# Switches.net
KiCad netlist of a schematic drawn in Altium Designer
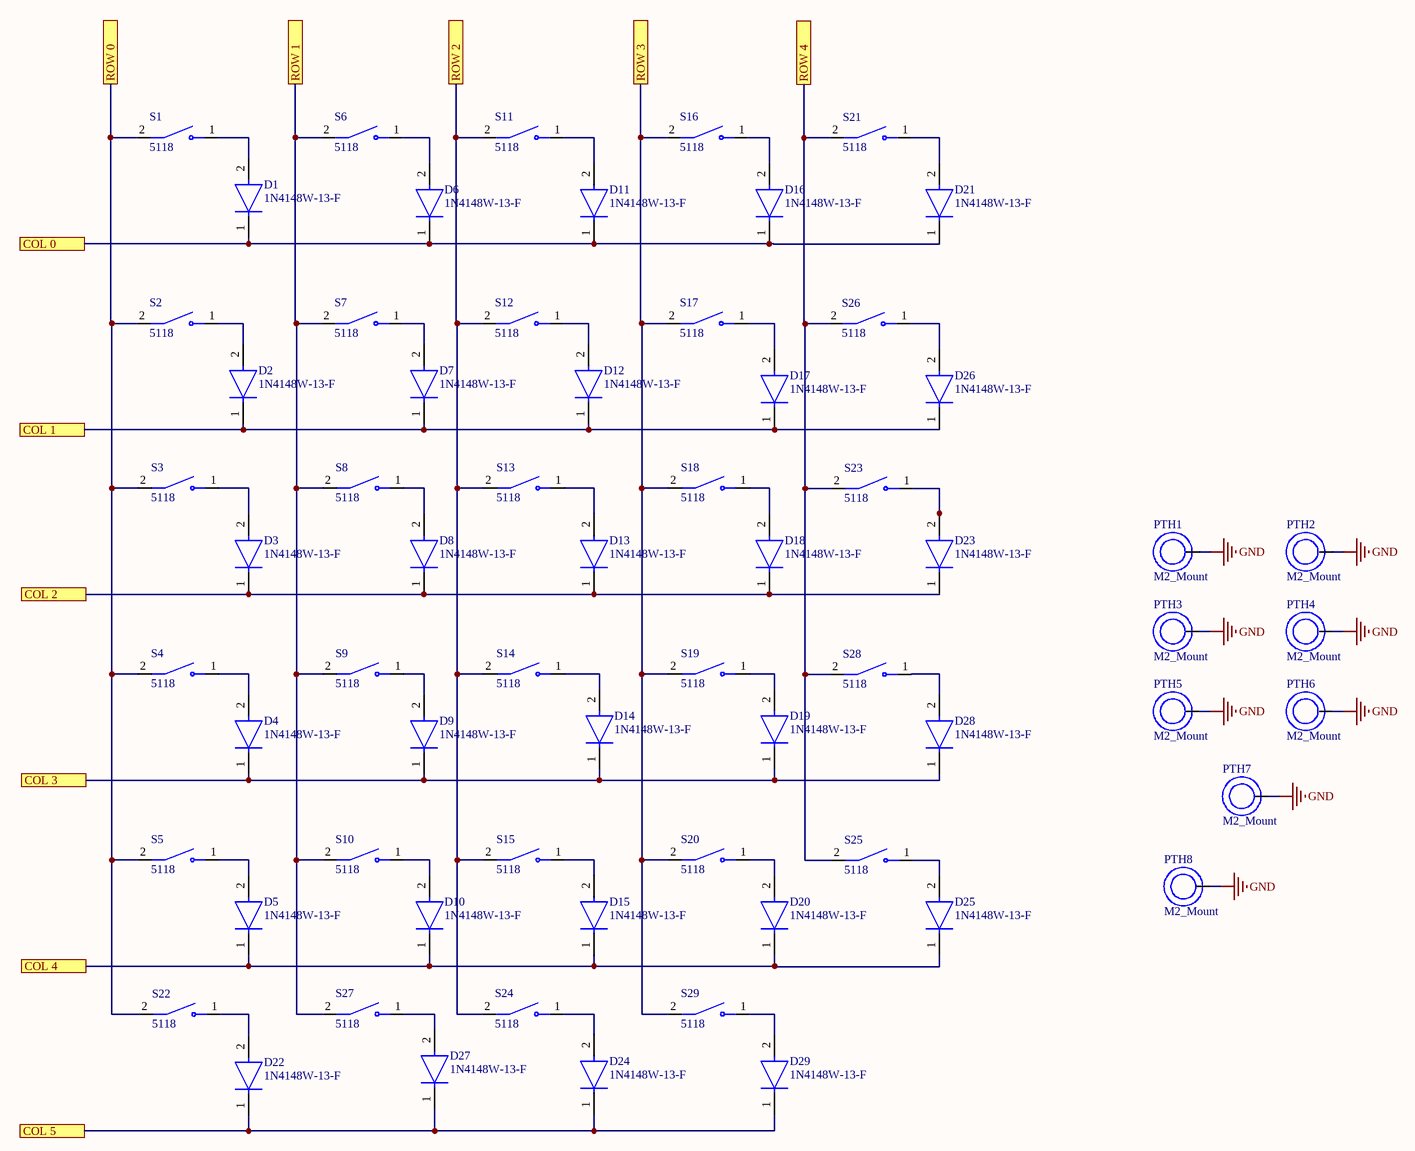
[diagram p0: Switches.SchDoc]

(export (version "E")
  (design (tool "Eeschema 10.0.6"))
  (components
    (comp (ref "D1")
      (value "1N4148W-13-F")
      (footprint "FP-SOD123-MFG")
      (description "DIODE GEN PURP 100V 150MA SOD123")
      (fields
        (field (name "OCTOPART") "https://octopart.com/1n4148w-13-f-diodes+inc.-2359612")
        (field (name "MANUFACTURER") "Diodes Inc.")
      )
      (libsource (lib "Altium Content Vault") (part "d7152d700b627762746794eb795d46e"))
    )
    (comp (ref "D2")
      (value "1N4148W-13-F")
      (footprint "FP-SOD123-MFG")
      (description "DIODE GEN PURP 100V 150MA SOD123")
      (fields
        (field (name "OCTOPART") "https://octopart.com/1n4148w-13-f-diodes+inc.-2359612")
        (field (name "MANUFACTURER") "Diodes Inc.")
      )
      (libsource (lib "Altium Content Vault") (part "d7152d700b627762746794eb795d46e"))
    )
    (comp (ref "D3")
      (value "1N4148W-13-F")
      (footprint "FP-SOD123-MFG")
      (description "DIODE GEN PURP 100V 150MA SOD123")
      (fields
        (field (name "OCTOPART") "https://octopart.com/1n4148w-13-f-diodes+inc.-2359612")
        (field (name "MANUFACTURER") "Diodes Inc.")
      )
      (libsource (lib "Altium Content Vault") (part "d7152d700b627762746794eb795d46e"))
    )
    (comp (ref "D4")
      (value "1N4148W-13-F")
      (footprint "FP-SOD123-MFG")
      (description "DIODE GEN PURP 100V 150MA SOD123")
      (fields
        (field (name "OCTOPART") "https://octopart.com/1n4148w-13-f-diodes+inc.-2359612")
        (field (name "MANUFACTURER") "Diodes Inc.")
      )
      (libsource (lib "Altium Content Vault") (part "d7152d700b627762746794eb795d46e"))
    )
    (comp (ref "D5")
      (value "1N4148W-13-F")
      (footprint "FP-SOD123-MFG")
      (description "DIODE GEN PURP 100V 150MA SOD123")
      (fields
        (field (name "OCTOPART") "https://octopart.com/1n4148w-13-f-diodes+inc.-2359612")
        (field (name "MANUFACTURER") "Diodes Inc.")
      )
      (libsource (lib "Altium Content Vault") (part "d7152d700b627762746794eb795d46e"))
    )
    (comp (ref "D6")
      (value "1N4148W-13-F")
      (footprint "FP-SOD123-MFG")
      (description "DIODE GEN PURP 100V 150MA SOD123")
      (fields
        (field (name "OCTOPART") "https://octopart.com/1n4148w-13-f-diodes+inc.-2359612")
        (field (name "MANUFACTURER") "Diodes Inc.")
      )
      (libsource (lib "Altium Content Vault") (part "d7152d700b627762746794eb795d46e"))
    )
    (comp (ref "D7")
      (value "1N4148W-13-F")
      (footprint "FP-SOD123-MFG")
      (description "DIODE GEN PURP 100V 150MA SOD123")
      (fields
        (field (name "OCTOPART") "https://octopart.com/1n4148w-13-f-diodes+inc.-2359612")
        (field (name "MANUFACTURER") "Diodes Inc.")
      )
      (libsource (lib "Altium Content Vault") (part "d7152d700b627762746794eb795d46e"))
    )
    (comp (ref "D8")
      (value "1N4148W-13-F")
      (footprint "FP-SOD123-MFG")
      (description "DIODE GEN PURP 100V 150MA SOD123")
      (fields
        (field (name "OCTOPART") "https://octopart.com/1n4148w-13-f-diodes+inc.-2359612")
        (field (name "MANUFACTURER") "Diodes Inc.")
      )
      (libsource (lib "Altium Content Vault") (part "d7152d700b627762746794eb795d46e"))
    )
    (comp (ref "D9")
      (value "1N4148W-13-F")
      (footprint "FP-SOD123-MFG")
      (description "DIODE GEN PURP 100V 150MA SOD123")
      (fields
        (field (name "OCTOPART") "https://octopart.com/1n4148w-13-f-diodes+inc.-2359612")
        (field (name "MANUFACTURER") "Diodes Inc.")
      )
      (libsource (lib "Altium Content Vault") (part "d7152d700b627762746794eb795d46e"))
    )
    (comp (ref "D10")
      (value "1N4148W-13-F")
      (footprint "FP-SOD123-MFG")
      (description "DIODE GEN PURP 100V 150MA SOD123")
      (fields
        (field (name "OCTOPART") "https://octopart.com/1n4148w-13-f-diodes+inc.-2359612")
        (field (name "MANUFACTURER") "Diodes Inc.")
      )
      (libsource (lib "Altium Content Vault") (part "d7152d700b627762746794eb795d46e"))
    )
    (comp (ref "D11")
      (value "1N4148W-13-F")
      (footprint "FP-SOD123-MFG")
      (description "DIODE GEN PURP 100V 150MA SOD123")
      (fields
        (field (name "OCTOPART") "https://octopart.com/1n4148w-13-f-diodes+inc.-2359612")
        (field (name "MANUFACTURER") "Diodes Inc.")
      )
      (libsource (lib "Altium Content Vault") (part "d7152d700b627762746794eb795d46e"))
    )
    (comp (ref "D12")
      (value "1N4148W-13-F")
      (footprint "FP-SOD123-MFG")
      (description "DIODE GEN PURP 100V 150MA SOD123")
      (fields
        (field (name "OCTOPART") "https://octopart.com/1n4148w-13-f-diodes+inc.-2359612")
        (field (name "MANUFACTURER") "Diodes Inc.")
      )
      (libsource (lib "Altium Content Vault") (part "d7152d700b627762746794eb795d46e"))
    )
    (comp (ref "D13")
      (value "1N4148W-13-F")
      (footprint "FP-SOD123-MFG")
      (description "DIODE GEN PURP 100V 150MA SOD123")
      (fields
        (field (name "OCTOPART") "https://octopart.com/1n4148w-13-f-diodes+inc.-2359612")
        (field (name "MANUFACTURER") "Diodes Inc.")
      )
      (libsource (lib "Altium Content Vault") (part "d7152d700b627762746794eb795d46e"))
    )
    (comp (ref "D14")
      (value "1N4148W-13-F")
      (footprint "FP-SOD123-MFG")
      (description "DIODE GEN PURP 100V 150MA SOD123")
      (fields
        (field (name "OCTOPART") "https://octopart.com/1n4148w-13-f-diodes+inc.-2359612")
        (field (name "MANUFACTURER") "Diodes Inc.")
      )
      (libsource (lib "Altium Content Vault") (part "d7152d700b627762746794eb795d46e"))
    )
    (comp (ref "D15")
      (value "1N4148W-13-F")
      (footprint "FP-SOD123-MFG")
      (description "DIODE GEN PURP 100V 150MA SOD123")
      (fields
        (field (name "OCTOPART") "https://octopart.com/1n4148w-13-f-diodes+inc.-2359612")
        (field (name "MANUFACTURER") "Diodes Inc.")
      )
      (libsource (lib "Altium Content Vault") (part "d7152d700b627762746794eb795d46e"))
    )
    (comp (ref "D16")
      (value "1N4148W-13-F")
      (footprint "FP-SOD123-MFG")
      (description "DIODE GEN PURP 100V 150MA SOD123")
      (fields
        (field (name "OCTOPART") "https://octopart.com/1n4148w-13-f-diodes+inc.-2359612")
        (field (name "MANUFACTURER") "Diodes Inc.")
      )
      (libsource (lib "Altium Content Vault") (part "d7152d700b627762746794eb795d46e"))
    )
    (comp (ref "D17")
      (value "1N4148W-13-F")
      (footprint "FP-SOD123-MFG")
      (description "DIODE GEN PURP 100V 150MA SOD123")
      (fields
        (field (name "OCTOPART") "https://octopart.com/1n4148w-13-f-diodes+inc.-2359612")
        (field (name "MANUFACTURER") "Diodes Inc.")
      )
      (libsource (lib "Altium Content Vault") (part "d7152d700b627762746794eb795d46e"))
    )
    (comp (ref "D18")
      (value "1N4148W-13-F")
      (footprint "FP-SOD123-MFG")
      (description "DIODE GEN PURP 100V 150MA SOD123")
      (fields
        (field (name "OCTOPART") "https://octopart.com/1n4148w-13-f-diodes+inc.-2359612")
        (field (name "MANUFACTURER") "Diodes Inc.")
      )
      (libsource (lib "Altium Content Vault") (part "d7152d700b627762746794eb795d46e"))
    )
    (comp (ref "D19")
      (value "1N4148W-13-F")
      (footprint "FP-SOD123-MFG")
      (description "DIODE GEN PURP 100V 150MA SOD123")
      (fields
        (field (name "OCTOPART") "https://octopart.com/1n4148w-13-f-diodes+inc.-2359612")
        (field (name "MANUFACTURER") "Diodes Inc.")
      )
      (libsource (lib "Altium Content Vault") (part "d7152d700b627762746794eb795d46e"))
    )
    (comp (ref "D20")
      (value "1N4148W-13-F")
      (footprint "FP-SOD123-MFG")
      (description "DIODE GEN PURP 100V 150MA SOD123")
      (fields
        (field (name "OCTOPART") "https://octopart.com/1n4148w-13-f-diodes+inc.-2359612")
        (field (name "MANUFACTURER") "Diodes Inc.")
      )
      (libsource (lib "Altium Content Vault") (part "d7152d700b627762746794eb795d46e"))
    )
    (comp (ref "D21")
      (value "1N4148W-13-F")
      (footprint "FP-SOD123-MFG")
      (description "DIODE GEN PURP 100V 150MA SOD123")
      (fields
        (field (name "OCTOPART") "https://octopart.com/1n4148w-13-f-diodes+inc.-2359612")
        (field (name "MANUFACTURER") "Diodes Inc.")
      )
      (libsource (lib "Altium Content Vault") (part "d7152d700b627762746794eb795d46e"))
    )
    (comp (ref "D22")
      (value "1N4148W-13-F")
      (footprint "FP-SOD123-MFG")
      (description "DIODE GEN PURP 100V 150MA SOD123")
      (fields
        (field (name "OCTOPART") "https://octopart.com/1n4148w-13-f-diodes+inc.-2359612")
        (field (name "MANUFACTURER") "Diodes Inc.")
      )
      (libsource (lib "Altium Content Vault") (part "d7152d700b627762746794eb795d46e"))
    )
    (comp (ref "D23")
      (value "1N4148W-13-F")
      (footprint "FP-SOD123-MFG")
      (description "DIODE GEN PURP 100V 150MA SOD123")
      (fields
        (field (name "OCTOPART") "https://octopart.com/1n4148w-13-f-diodes+inc.-2359612")
        (field (name "MANUFACTURER") "Diodes Inc.")
      )
      (libsource (lib "Altium Content Vault") (part "d7152d700b627762746794eb795d46e"))
    )
    (comp (ref "D24")
      (value "1N4148W-13-F")
      (footprint "FP-SOD123-MFG")
      (description "DIODE GEN PURP 100V 150MA SOD123")
      (fields
        (field (name "OCTOPART") "https://octopart.com/1n4148w-13-f-diodes+inc.-2359612")
        (field (name "MANUFACTURER") "Diodes Inc.")
      )
      (libsource (lib "Altium Content Vault") (part "d7152d700b627762746794eb795d46e"))
    )
    (comp (ref "D25")
      (value "1N4148W-13-F")
      (footprint "FP-SOD123-MFG")
      (description "DIODE GEN PURP 100V 150MA SOD123")
      (fields
        (field (name "OCTOPART") "https://octopart.com/1n4148w-13-f-diodes+inc.-2359612")
        (field (name "MANUFACTURER") "Diodes Inc.")
      )
      (libsource (lib "Altium Content Vault") (part "d7152d700b627762746794eb795d46e"))
    )
    (comp (ref "D26")
      (value "1N4148W-13-F")
      (footprint "FP-SOD123-MFG")
      (description "DIODE GEN PURP 100V 150MA SOD123")
      (fields
        (field (name "OCTOPART") "https://octopart.com/1n4148w-13-f-diodes+inc.-2359612")
        (field (name "MANUFACTURER") "Diodes Inc.")
      )
      (libsource (lib "Altium Content Vault") (part "d7152d700b627762746794eb795d46e"))
    )
    (comp (ref "D27")
      (value "1N4148W-13-F")
      (footprint "FP-SOD123-MFG")
      (description "DIODE GEN PURP 100V 150MA SOD123")
      (fields
        (field (name "OCTOPART") "https://octopart.com/1n4148w-13-f-diodes+inc.-2359612")
        (field (name "MANUFACTURER") "Diodes Inc.")
      )
      (libsource (lib "Altium Content Vault") (part "d7152d700b627762746794eb795d46e"))
    )
    (comp (ref "D28")
      (value "1N4148W-13-F")
      (footprint "FP-SOD123-MFG")
      (description "DIODE GEN PURP 100V 150MA SOD123")
      (fields
        (field (name "OCTOPART") "https://octopart.com/1n4148w-13-f-diodes+inc.-2359612")
        (field (name "MANUFACTURER") "Diodes Inc.")
      )
      (libsource (lib "Altium Content Vault") (part "d7152d700b627762746794eb795d46e"))
    )
    (comp (ref "D29")
      (value "1N4148W-13-F")
      (footprint "FP-SOD123-MFG")
      (description "DIODE GEN PURP 100V 150MA SOD123")
      (fields
        (field (name "OCTOPART") "https://octopart.com/1n4148w-13-f-diodes+inc.-2359612")
        (field (name "MANUFACTURER") "Diodes Inc.")
      )
      (libsource (lib "Altium Content Vault") (part "d7152d700b627762746794eb795d46e"))
    )
    (comp (ref "PTH1")
      (value "M2_Mount")
      (footprint "Mounting_Holes")
      (libsource (lib "Mounting_Holes") (part "M2_Mount"))
    )
    (comp (ref "PTH2")
      (value "M2_Mount")
      (footprint "Mounting_Holes")
      (libsource (lib "Mounting_Holes") (part "M2_Mount"))
    )
    (comp (ref "PTH3")
      (value "M2_Mount")
      (footprint "Mounting_Holes")
      (libsource (lib "Mounting_Holes") (part "M2_Mount"))
    )
    (comp (ref "PTH4")
      (value "M2_Mount")
      (footprint "Mounting_Holes")
      (libsource (lib "Mounting_Holes") (part "M2_Mount"))
    )
    (comp (ref "PTH5")
      (value "M2_Mount")
      (footprint "Mounting_Holes")
      (libsource (lib "Mounting_Holes") (part "M2_Mount"))
    )
    (comp (ref "PTH6")
      (value "M2_Mount")
      (footprint "Mounting_Holes")
      (libsource (lib "Mounting_Holes") (part "M2_Mount"))
    )
    (comp (ref "PTH7")
      (value "M2_Mount")
      (footprint "Mounting_Holes")
      (libsource (lib "Mounting_Holes") (part "M2_Mount"))
    )
    (comp (ref "PTH8")
      (value "M2_Mount")
      (footprint "Mounting_Holes")
      (libsource (lib "Mounting_Holes") (part "M2_Mount"))
    )
    (comp (ref "S1")
      (value "5118")
      (footprint "5118:SW_5118")
      (description "SWITCH SKT FOR KAILH CHOC 1=10PC")
      (fields (field (name "MF") "Adafruit Industries LLC"))
      (libsource (lib "*") (part "5118"))
    )
    (comp (ref "S2")
      (value "5118")
      (footprint "5118:SW_5118")
      (description "SWITCH SKT FOR KAILH CHOC 1=10PC")
      (fields (field (name "MF") "Adafruit Industries LLC"))
      (libsource (lib "*") (part "5118"))
    )
    (comp (ref "S3")
      (value "5118")
      (footprint "5118:SW_5118")
      (description "SWITCH SKT FOR KAILH CHOC 1=10PC")
      (fields (field (name "MF") "Adafruit Industries LLC"))
      (libsource (lib "*") (part "5118"))
    )
    (comp (ref "S4")
      (value "5118")
      (footprint "5118:SW_5118")
      (description "SWITCH SKT FOR KAILH CHOC 1=10PC")
      (fields (field (name "MF") "Adafruit Industries LLC"))
      (libsource (lib "*") (part "5118"))
    )
    (comp (ref "S5")
      (value "5118")
      (footprint "5118:SW_5118")
      (description "SWITCH SKT FOR KAILH CHOC 1=10PC")
      (fields (field (name "MF") "Adafruit Industries LLC"))
      (libsource (lib "*") (part "5118"))
    )
    (comp (ref "S6")
      (value "5118")
      (footprint "5118:SW_5118")
      (description "SWITCH SKT FOR KAILH CHOC 1=10PC")
      (fields (field (name "MF") "Adafruit Industries LLC"))
      (libsource (lib "*") (part "5118"))
    )
    (comp (ref "S7")
      (value "5118")
      (footprint "5118:SW_5118")
      (description "SWITCH SKT FOR KAILH CHOC 1=10PC")
      (fields (field (name "MF") "Adafruit Industries LLC"))
      (libsource (lib "*") (part "5118"))
    )
    (comp (ref "S8")
      (value "5118")
      (footprint "5118:SW_5118")
      (description "SWITCH SKT FOR KAILH CHOC 1=10PC")
      (fields (field (name "MF") "Adafruit Industries LLC"))
      (libsource (lib "*") (part "5118"))
    )
    (comp (ref "S9")
      (value "5118")
      (footprint "5118:SW_5118")
      (description "SWITCH SKT FOR KAILH CHOC 1=10PC")
      (fields (field (name "MF") "Adafruit Industries LLC"))
      (libsource (lib "*") (part "5118"))
    )
    (comp (ref "S10")
      (value "5118")
      (footprint "5118:SW_5118")
      (description "SWITCH SKT FOR KAILH CHOC 1=10PC")
      (fields (field (name "MF") "Adafruit Industries LLC"))
      (libsource (lib "*") (part "5118"))
    )
    (comp (ref "S11")
      (value "5118")
      (footprint "5118:SW_5118")
      (description "SWITCH SKT FOR KAILH CHOC 1=10PC")
      (fields (field (name "MF") "Adafruit Industries LLC"))
      (libsource (lib "*") (part "5118"))
    )
    (comp (ref "S12")
      (value "5118")
      (footprint "5118:SW_5118")
      (description "SWITCH SKT FOR KAILH CHOC 1=10PC")
      (fields (field (name "MF") "Adafruit Industries LLC"))
      (libsource (lib "*") (part "5118"))
    )
    (comp (ref "S13")
      (value "5118")
      (footprint "5118:SW_5118")
      (description "SWITCH SKT FOR KAILH CHOC 1=10PC")
      (fields (field (name "MF") "Adafruit Industries LLC"))
      (libsource (lib "*") (part "5118"))
    )
    (comp (ref "S14")
      (value "5118")
      (footprint "5118:SW_5118")
      (description "SWITCH SKT FOR KAILH CHOC 1=10PC")
      (fields (field (name "MF") "Adafruit Industries LLC"))
      (libsource (lib "*") (part "5118"))
    )
    (comp (ref "S15")
      (value "5118")
      (footprint "5118:SW_5118")
      (description "SWITCH SKT FOR KAILH CHOC 1=10PC")
      (fields (field (name "MF") "Adafruit Industries LLC"))
      (libsource (lib "*") (part "5118"))
    )
    (comp (ref "S16")
      (value "5118")
      (footprint "5118:SW_5118")
      (description "SWITCH SKT FOR KAILH CHOC 1=10PC")
      (fields (field (name "MF") "Adafruit Industries LLC"))
      (libsource (lib "*") (part "5118"))
    )
    (comp (ref "S17")
      (value "5118")
      (footprint "5118:SW_5118")
      (description "SWITCH SKT FOR KAILH CHOC 1=10PC")
      (fields (field (name "MF") "Adafruit Industries LLC"))
      (libsource (lib "*") (part "5118"))
    )
    (comp (ref "S18")
      (value "5118")
      (footprint "5118:SW_5118")
      (description "SWITCH SKT FOR KAILH CHOC 1=10PC")
      (fields (field (name "MF") "Adafruit Industries LLC"))
      (libsource (lib "*") (part "5118"))
    )
    (comp (ref "S19")
      (value "5118")
      (footprint "5118:SW_5118")
      (description "SWITCH SKT FOR KAILH CHOC 1=10PC")
      (fields (field (name "MF") "Adafruit Industries LLC"))
      (libsource (lib "*") (part "5118"))
    )
    (comp (ref "S20")
      (value "5118")
      (footprint "5118:SW_5118")
      (description "SWITCH SKT FOR KAILH CHOC 1=10PC")
      (fields (field (name "MF") "Adafruit Industries LLC"))
      (libsource (lib "*") (part "5118"))
    )
    (comp (ref "S21")
      (value "5118")
      (footprint "5118:SW_5118")
      (description "SWITCH SKT FOR KAILH CHOC 1=10PC")
      (fields (field (name "MF") "Adafruit Industries LLC"))
      (libsource (lib "") (part "5118_1"))
    )
    (comp (ref "S22")
      (value "5118")
      (footprint "5118:SW_5118")
      (description "SWITCH SKT FOR KAILH CHOC 1=10PC")
      (fields (field (name "MF") "Adafruit Industries LLC"))
      (libsource (lib "*") (part "5118"))
    )
    (comp (ref "S23")
      (value "5118")
      (footprint "5118:SW_5118")
      (description "SWITCH SKT FOR KAILH CHOC 1=10PC")
      (fields (field (name "MF") "Adafruit Industries LLC"))
      (libsource (lib "*") (part "5118"))
    )
    (comp (ref "S24")
      (value "5118")
      (footprint "5118:SW_5118")
      (description "SWITCH SKT FOR KAILH CHOC 1=10PC")
      (fields (field (name "MF") "Adafruit Industries LLC"))
      (libsource (lib "*") (part "5118"))
    )
    (comp (ref "S25")
      (value "5118")
      (footprint "5118:SW_5118")
      (description "SWITCH SKT FOR KAILH CHOC 1=10PC")
      (fields (field (name "MF") "Adafruit Industries LLC"))
      (libsource (lib "*") (part "5118"))
    )
    (comp (ref "S26")
      (value "5118")
      (footprint "5118:SW_5118")
      (description "SWITCH SKT FOR KAILH CHOC 1=10PC")
      (fields (field (name "MF") "Adafruit Industries LLC"))
      (libsource (lib "*") (part "5118"))
    )
    (comp (ref "S27")
      (value "5118")
      (footprint "5118:SW_5118")
      (description "SWITCH SKT FOR KAILH CHOC 1=10PC")
      (fields (field (name "MF") "Adafruit Industries LLC"))
      (libsource (lib "*") (part "5118"))
    )
    (comp (ref "S28")
      (value "5118")
      (footprint "5118:SW_5118")
      (description "SWITCH SKT FOR KAILH CHOC 1=10PC")
      (fields (field (name "MF") "Adafruit Industries LLC"))
      (libsource (lib "*") (part "5118"))
    )
    (comp (ref "S29")
      (value "5118")
      (footprint "5118:SW_5118")
      (description "SWITCH SKT FOR KAILH CHOC 1=10PC")
      (fields (field (name "MF") "Adafruit Industries LLC"))
      (libsource (lib "*") (part "5118"))
    )
  )
  (nets
    (net (code "2") (name "/COL 0") (class "Default")
      (node (ref "D1") (pin "1") (pinfunction "C_1") (pintype "passive"))
      (node (ref "D11") (pin "1") (pinfunction "C_1") (pintype "passive"))
      (node (ref "D16") (pin "1") (pinfunction "C_1") (pintype "passive"))
      (node (ref "D21") (pin "1") (pinfunction "C_1") (pintype "passive"))
      (node (ref "D6") (pin "1") (pinfunction "C_1") (pintype "passive"))
    )
    (net (code "4") (name "/COL 1") (class "Default")
      (node (ref "D12") (pin "1") (pinfunction "C_1") (pintype "passive"))
      (node (ref "D17") (pin "1") (pinfunction "C_1") (pintype "passive"))
      (node (ref "D2") (pin "1") (pinfunction "C_1") (pintype "passive"))
      (node (ref "D26") (pin "1") (pinfunction "C_1") (pintype "passive"))
      (node (ref "D7") (pin "1") (pinfunction "C_1") (pintype "passive"))
    )
    (net (code "5") (name "/COL 2") (class "Default")
      (node (ref "D13") (pin "1") (pinfunction "C_1") (pintype "passive"))
      (node (ref "D18") (pin "1") (pinfunction "C_1") (pintype "passive"))
      (node (ref "D23") (pin "1") (pinfunction "C_1") (pintype "passive"))
      (node (ref "D3") (pin "1") (pinfunction "C_1") (pintype "passive"))
      (node (ref "D8") (pin "1") (pinfunction "C_1") (pintype "passive"))
    )
    (net (code "6") (name "/COL 3") (class "Default")
      (node (ref "D14") (pin "1") (pinfunction "C_1") (pintype "passive"))
      (node (ref "D19") (pin "1") (pinfunction "C_1") (pintype "passive"))
      (node (ref "D28") (pin "1") (pinfunction "C_1") (pintype "passive"))
      (node (ref "D4") (pin "1") (pinfunction "C_1") (pintype "passive"))
      (node (ref "D9") (pin "1") (pinfunction "C_1") (pintype "passive"))
    )
    (net (code "7") (name "/COL 4") (class "Default")
      (node (ref "D10") (pin "1") (pinfunction "C_1") (pintype "passive"))
      (node (ref "D15") (pin "1") (pinfunction "C_1") (pintype "passive"))
      (node (ref "D20") (pin "1") (pinfunction "C_1") (pintype "passive"))
      (node (ref "D25") (pin "1") (pinfunction "C_1") (pintype "passive"))
      (node (ref "D5") (pin "1") (pinfunction "C_1") (pintype "passive"))
    )
    (net (code "8") (name "/COL 5") (class "Default")
      (node (ref "D22") (pin "1") (pinfunction "C_1") (pintype "passive"))
      (node (ref "D24") (pin "1") (pinfunction "C_1") (pintype "passive"))
      (node (ref "D27") (pin "1") (pinfunction "C_1") (pintype "passive"))
      (node (ref "D29") (pin "1") (pinfunction "C_1") (pintype "passive"))
    )
    (net (code "9") (name "/ROW 0") (class "Default")
      (node (ref "S1") (pin "2") (pinfunction "COM_2") (pintype "passive"))
      (node (ref "S2") (pin "2") (pinfunction "COM_2") (pintype "passive"))
      (node (ref "S22") (pin "2") (pinfunction "COM_2") (pintype "passive"))
      (node (ref "S3") (pin "2") (pinfunction "COM_2") (pintype "passive"))
      (node (ref "S4") (pin "2") (pinfunction "COM_2") (pintype "passive"))
      (node (ref "S5") (pin "2") (pinfunction "COM_2") (pintype "passive"))
    )
    (net (code "10") (name "/ROW 1") (class "Default")
      (node (ref "S10") (pin "2") (pinfunction "COM_2") (pintype "passive"))
      (node (ref "S27") (pin "2") (pinfunction "COM_2") (pintype "passive"))
      (node (ref "S6") (pin "2") (pinfunction "COM_2") (pintype "passive"))
      (node (ref "S7") (pin "2") (pinfunction "COM_2") (pintype "passive"))
      (node (ref "S8") (pin "2") (pinfunction "COM_2") (pintype "passive"))
      (node (ref "S9") (pin "2") (pinfunction "COM_2") (pintype "passive"))
    )
    (net (code "11") (name "/ROW 2") (class "Default")
      (node (ref "S11") (pin "2") (pinfunction "COM_2") (pintype "passive"))
      (node (ref "S12") (pin "2") (pinfunction "COM_2") (pintype "passive"))
      (node (ref "S13") (pin "2") (pinfunction "COM_2") (pintype "passive"))
      (node (ref "S14") (pin "2") (pinfunction "COM_2") (pintype "passive"))
      (node (ref "S15") (pin "2") (pinfunction "COM_2") (pintype "passive"))
      (node (ref "S24") (pin "2") (pinfunction "COM_2") (pintype "passive"))
    )
    (net (code "12") (name "/ROW 3") (class "Default")
      (node (ref "S16") (pin "2") (pinfunction "COM_2") (pintype "passive"))
      (node (ref "S17") (pin "2") (pinfunction "COM_2") (pintype "passive"))
      (node (ref "S18") (pin "2") (pinfunction "COM_2") (pintype "passive"))
      (node (ref "S19") (pin "2") (pinfunction "COM_2") (pintype "passive"))
      (node (ref "S20") (pin "2") (pinfunction "COM_2") (pintype "passive"))
      (node (ref "S29") (pin "2") (pinfunction "COM_2") (pintype "passive"))
    )
    (net (code "13") (name "/ROW 4") (class "Default")
      (node (ref "S21") (pin "2") (pinfunction "COM_2") (pintype "passive"))
      (node (ref "S23") (pin "2") (pinfunction "COM_2") (pintype "passive"))
      (node (ref "S25") (pin "2") (pinfunction "COM_2") (pintype "passive"))
      (node (ref "S26") (pin "2") (pinfunction "COM_2") (pintype "passive"))
      (node (ref "S28") (pin "2") (pinfunction "COM_2") (pintype "passive"))
    )
    (net (code "14") (name "GND") (class "Default")
      (node (ref "PTH1") (pin "0") (pinfunction "0_0") (pintype "passive"))
      (node (ref "PTH2") (pin "0") (pinfunction "0_0") (pintype "passive"))
      (node (ref "PTH3") (pin "0") (pinfunction "0_0") (pintype "passive"))
      (node (ref "PTH4") (pin "0") (pinfunction "0_0") (pintype "passive"))
      (node (ref "PTH5") (pin "0") (pinfunction "0_0") (pintype "passive"))
      (node (ref "PTH6") (pin "0") (pinfunction "0_0") (pintype "passive"))
      (node (ref "PTH7") (pin "0") (pinfunction "0_0") (pintype "passive"))
      (node (ref "PTH8") (pin "0") (pinfunction "0_0") (pintype "passive"))
    )
    (net (code "15") (name "Net-(D1-A)") (class "Default")
      (node (ref "D1") (pin "2") (pinfunction "A_2") (pintype "passive"))
      (node (ref "S1") (pin "1") (pinfunction "NO_1") (pintype "passive"))
    )
    (net (code "16") (name "Net-(D2-A)") (class "Default")
      (node (ref "D2") (pin "2") (pinfunction "A_2") (pintype "passive"))
      (node (ref "S2") (pin "1") (pinfunction "NO_1") (pintype "passive"))
    )
    (net (code "17") (name "Net-(D3-A)") (class "Default")
      (node (ref "D3") (pin "2") (pinfunction "A_2") (pintype "passive"))
      (node (ref "S3") (pin "1") (pinfunction "NO_1") (pintype "passive"))
    )
    (net (code "18") (name "Net-(D4-A)") (class "Default")
      (node (ref "D4") (pin "2") (pinfunction "A_2") (pintype "passive"))
      (node (ref "S4") (pin "1") (pinfunction "NO_1") (pintype "passive"))
    )
    (net (code "19") (name "Net-(D5-A)") (class "Default")
      (node (ref "D5") (pin "2") (pinfunction "A_2") (pintype "passive"))
      (node (ref "S5") (pin "1") (pinfunction "NO_1") (pintype "passive"))
    )
    (net (code "20") (name "Net-(D6-A)") (class "Default")
      (node (ref "D6") (pin "2") (pinfunction "A_2") (pintype "passive"))
      (node (ref "S6") (pin "1") (pinfunction "NO_1") (pintype "passive"))
    )
    (net (code "21") (name "Net-(D7-A)") (class "Default")
      (node (ref "D7") (pin "2") (pinfunction "A_2") (pintype "passive"))
      (node (ref "S7") (pin "1") (pinfunction "NO_1") (pintype "passive"))
    )
    (net (code "22") (name "Net-(D8-A)") (class "Default")
      (node (ref "D8") (pin "2") (pinfunction "A_2") (pintype "passive"))
      (node (ref "S8") (pin "1") (pinfunction "NO_1") (pintype "passive"))
    )
    (net (code "23") (name "Net-(D9-A)") (class "Default")
      (node (ref "D9") (pin "2") (pinfunction "A_2") (pintype "passive"))
      (node (ref "S9") (pin "1") (pinfunction "NO_1") (pintype "passive"))
    )
    (net (code "24") (name "Net-(D10-A)") (class "Default")
      (node (ref "D10") (pin "2") (pinfunction "A_2") (pintype "passive"))
      (node (ref "S10") (pin "1") (pinfunction "NO_1") (pintype "passive"))
    )
    (net (code "25") (name "Net-(D11-A)") (class "Default")
      (node (ref "D11") (pin "2") (pinfunction "A_2") (pintype "passive"))
      (node (ref "S11") (pin "1") (pinfunction "NO_1") (pintype "passive"))
    )
    (net (code "26") (name "Net-(D12-A)") (class "Default")
      (node (ref "D12") (pin "2") (pinfunction "A_2") (pintype "passive"))
      (node (ref "S12") (pin "1") (pinfunction "NO_1") (pintype "passive"))
    )
    (net (code "27") (name "Net-(D13-A)") (class "Default")
      (node (ref "D13") (pin "2") (pinfunction "A_2") (pintype "passive"))
      (node (ref "S13") (pin "1") (pinfunction "NO_1") (pintype "passive"))
    )
    (net (code "28") (name "Net-(D14-A)") (class "Default")
      (node (ref "D14") (pin "2") (pinfunction "A_2") (pintype "passive"))
      (node (ref "S14") (pin "1") (pinfunction "NO_1") (pintype "passive"))
    )
    (net (code "29") (name "Net-(D15-A)") (class "Default")
      (node (ref "D15") (pin "2") (pinfunction "A_2") (pintype "passive"))
      (node (ref "S15") (pin "1") (pinfunction "NO_1") (pintype "passive"))
    )
    (net (code "30") (name "Net-(D16-A)") (class "Default")
      (node (ref "D16") (pin "2") (pinfunction "A_2") (pintype "passive"))
      (node (ref "S16") (pin "1") (pinfunction "NO_1") (pintype "passive"))
    )
    (net (code "31") (name "Net-(D17-A)") (class "Default")
      (node (ref "D17") (pin "2") (pinfunction "A_2") (pintype "passive"))
      (node (ref "S17") (pin "1") (pinfunction "NO_1") (pintype "passive"))
    )
    (net (code "32") (name "Net-(D18-A)") (class "Default")
      (node (ref "D18") (pin "2") (pinfunction "A_2") (pintype "passive"))
      (node (ref "S18") (pin "1") (pinfunction "NO_1") (pintype "passive"))
    )
    (net (code "33") (name "Net-(D19-A)") (class "Default")
      (node (ref "D19") (pin "2") (pinfunction "A_2") (pintype "passive"))
      (node (ref "S19") (pin "1") (pinfunction "NO_1") (pintype "passive"))
    )
    (net (code "34") (name "Net-(D20-A)") (class "Default")
      (node (ref "D20") (pin "2") (pinfunction "A_2") (pintype "passive"))
      (node (ref "S20") (pin "1") (pinfunction "NO_1") (pintype "passive"))
    )
    (net (code "35") (name "Net-(D21-A)") (class "Default")
      (node (ref "D21") (pin "2") (pinfunction "A_2") (pintype "passive"))
      (node (ref "S21") (pin "1") (pinfunction "NO_1") (pintype "passive"))
    )
    (net (code "36") (name "Net-(D22-A)") (class "Default")
      (node (ref "D22") (pin "2") (pinfunction "A_2") (pintype "passive"))
      (node (ref "S22") (pin "1") (pinfunction "NO_1") (pintype "passive"))
    )
    (net (code "37") (name "Net-(D23-A)") (class "Default")
      (node (ref "D23") (pin "2") (pinfunction "A_2") (pintype "passive"))
      (node (ref "S23") (pin "1") (pinfunction "NO_1") (pintype "passive"))
    )
    (net (code "38") (name "Net-(D24-A)") (class "Default")
      (node (ref "D24") (pin "2") (pinfunction "A_2") (pintype "passive"))
      (node (ref "S24") (pin "1") (pinfunction "NO_1") (pintype "passive"))
    )
    (net (code "39") (name "Net-(D25-A)") (class "Default")
      (node (ref "D25") (pin "2") (pinfunction "A_2") (pintype "passive"))
      (node (ref "S25") (pin "1") (pinfunction "NO_1") (pintype "passive"))
    )
    (net (code "40") (name "Net-(D26-A)") (class "Default")
      (node (ref "D26") (pin "2") (pinfunction "A_2") (pintype "passive"))
      (node (ref "S26") (pin "1") (pinfunction "NO_1") (pintype "passive"))
    )
    (net (code "41") (name "Net-(D27-A)") (class "Default")
      (node (ref "D27") (pin "2") (pinfunction "A_2") (pintype "passive"))
      (node (ref "S27") (pin "1") (pinfunction "NO_1") (pintype "passive"))
    )
    (net (code "42") (name "Net-(D28-A)") (class "Default")
      (node (ref "D28") (pin "2") (pinfunction "A_2") (pintype "passive"))
      (node (ref "S28") (pin "1") (pinfunction "NO_1") (pintype "passive"))
    )
    (net (code "43") (name "Net-(D29-A)") (class "Default")
      (node (ref "D29") (pin "2") (pinfunction "A_2") (pintype "passive"))
      (node (ref "S29") (pin "1") (pinfunction "NO_1") (pintype "passive"))
    )
  )
)
